# Sheet1.net
KiCad netlist of a schematic drawn in Altium Designer
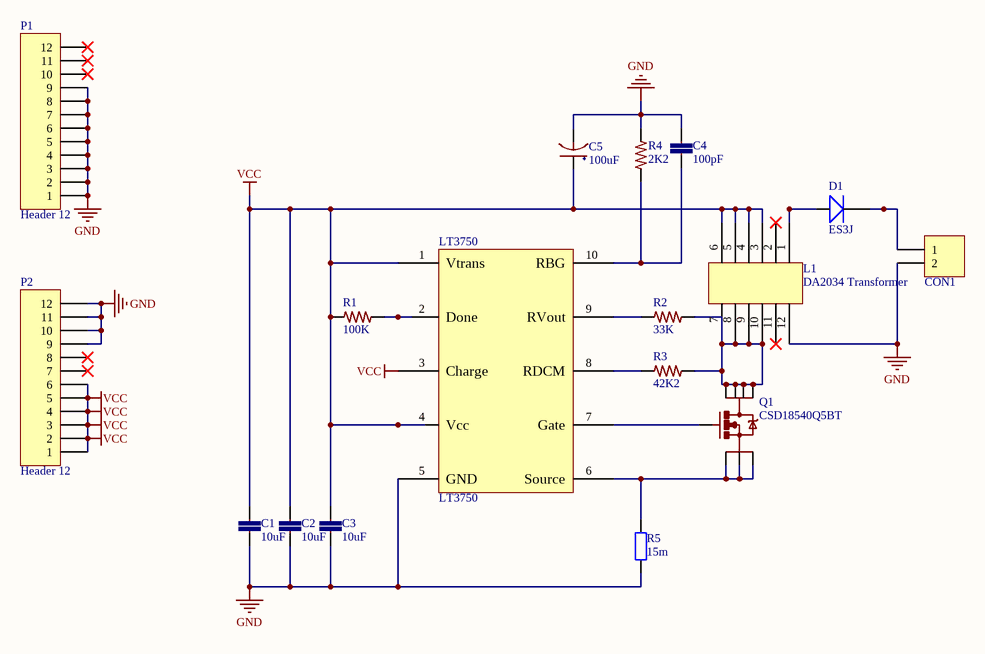
[diagram p0: Sheet1.SchDoc]

(export (version "E")
  (design (tool "Eeschema 10.0.6"))
  (components
    (comp (ref "C1")
      (value "10uF")
      (footprint "CAPC0603(1608)55_L")
      (description "CAP CER 10UF 16V X5R 0603")
      (fields (field (name "PART NO") "EMK107BBJ106MA-T"))
      (libsource (lib "IMBEL") (part "CAPACITOR"))
    )
    (comp (ref "C2")
      (value "10uF")
      (footprint "CAPC0603(1608)55_L")
      (description "CAP CER 10UF 16V X5R 0603")
      (fields (field (name "PART NO") "EMK107BBJ106MA-T"))
      (libsource (lib "IMBEL") (part "CAPACITOR"))
    )
    (comp (ref "C3")
      (value "10uF")
      (footprint "CAPC0603(1608)55_L")
      (description "CAP CER 10UF 16V X5R 0603")
      (fields (field (name "PART NO") "EMK107BBJ106MA-T"))
      (libsource (lib "IMBEL") (part "CAPACITOR"))
    )
    (comp (ref "C4")
      (value "100pF")
      (footprint "CAPC0603(1608)55_L")
      (description "CAP CER 100PF 50V NP0 0603")
      (fields (field (name "PART NO") "GRM1885C1H101JA01D"))
      (libsource (lib "IMBEL") (part "CAPACITOR"))
    )
    (comp (ref "C5")
      (value "100uF")
      (footprint "PCBComponent")
      (description "CAP ALUM 100UF 20% 80V SMD")
      (libsource (lib "IMBEL") (part "CAPACITOR-POL"))
    )
    (comp (ref "CON1")
      (value "OSTTA024163")
      (footprint "Term Block 2P")
      (description "2 Position Wire to Board Terminal Block Horizontal with Board 0.200\" (5.08mm) Through Hole")
      (libsource (lib "Schlib1") (part "Term Block 2P"))
    )
    (comp (ref "D1") (value "ES3J") (footprint "Diode") (libsource (lib "Schlib1") (part "Diode")))
    (comp (ref "L1")
      (value "DA2034 Transformer")
      (footprint "DA2034 Transformer")
      (libsource (lib "Schlib1") (part "DA2034 Transformer"))
    )
    (comp (ref "LT3750") (value "LT3750") (footprint "LT3750") (libsource (lib "Schlib1") (part "LT3750")))
    (comp (ref "P1")
      (value "Header 12")
      (footprint "HDR1X12")
      (description "Header, 12-Pin")
      (fields (field (name "PUBLISHER") "Altium Limited"))
      (libsource (lib "Miscellaneous Connectors") (part "Header 12"))
    )
    (comp (ref "P2")
      (value "Header 12")
      (footprint "HDR1X12")
      (description "Header, 12-Pin")
      (fields (field (name "PUBLISHER") "Altium Limited"))
      (libsource (lib "Miscellaneous Connectors") (part "Header 12"))
    )
    (comp (ref "Q1")
      (value "CSD18540Q5BT")
      (footprint "PCBComponent")
      (description "MOSFET N-CH 60V 100A 8VSON")
      (libsource (lib "IMBEL") (part "MOSFET-NCHANNEL"))
    )
    (comp (ref "R1")
      (value "100K")
      (footprint "0402-RES-HD")
      (description "RES 100K OHM 1/10W 1% 0402 SMD 1")
      (fields (field (name "PART NO") "ERJ-2GEJ104X"))
      (libsource (lib "IMBEL") (part "RESISTOR"))
    )
    (comp (ref "R2")
      (value "33K")
      (footprint "0402-RES-HD")
      (description "RES 33K OHM 1/10W 1% 0402 SMD")
      (fields (field (name "PART NO") "ERJ-2RKF3302X"))
      (libsource (lib "IMBEL") (part "RESISTOR"))
    )
    (comp (ref "R3")
      (value "42K2")
      (footprint "0402-RES-HD")
      (description "RES 42.2K OHM 1/10W 1% 0402 SMD")
      (fields (field (name "PART NO") "ERJ-2RKF4222X"))
      (libsource (lib "IMBEL") (part "RESISTOR"))
    )
    (comp (ref "R4")
      (value "2K2")
      (footprint "0402-RES-HD")
      (description "RES 2.2K OHM 1/10W 1% 0402 SMD")
      (fields (field (name "PART NO") "ERJ-2RKF2201X"))
      (libsource (lib "IMBEL") (part "RESISTOR"))
    )
    (comp (ref "R5")
      (value "15m")
      (footprint "RES-1206")
      (description "RES 15m OHM 1W 1% 1210 SMD")
      (fields (field (name "PUBLISHER") "Altium Limited"))
      (libsource (lib "Schlib1") (part "Res2"))
    )
  )
  (nets
    (net (code "1") (name "GND") (class "Default")
      (node (ref "C1") (pin "2") (pinfunction "2_2") (pintype "passive"))
      (node (ref "C2") (pin "2") (pinfunction "2_2") (pintype "passive"))
      (node (ref "C3") (pin "2") (pinfunction "2_2") (pintype "passive"))
      (node (ref "C4") (pin "1") (pinfunction "1_1") (pintype "passive"))
      (node (ref "C5") (pin "2") (pinfunction "-_2") (pintype "passive"))
      (node (ref "CON1") (pin "2") (pinfunction "2_2") (pintype "passive"))
      (node (ref "L1") (pin "12") (pinfunction "12_12") (pintype "passive"))
      (node (ref "LT3750") (pin "5") (pinfunction "GND_5") (pintype "passive"))
      (node (ref "P1") (pin "1") (pinfunction "1_1") (pintype "passive"))
      (node (ref "P1") (pin "2") (pinfunction "2_2") (pintype "passive"))
      (node (ref "P1") (pin "3") (pinfunction "3_3") (pintype "passive"))
      (node (ref "P1") (pin "4") (pinfunction "4_4") (pintype "passive"))
      (node (ref "P1") (pin "5") (pinfunction "5_5") (pintype "passive"))
      (node (ref "P1") (pin "6") (pinfunction "6_6") (pintype "passive"))
      (node (ref "P1") (pin "7") (pinfunction "7_7") (pintype "passive"))
      (node (ref "P1") (pin "8") (pinfunction "8_8") (pintype "passive"))
      (node (ref "P1") (pin "9") (pinfunction "9_9") (pintype "passive"))
      (node (ref "P2") (pin "10") (pinfunction "10_10") (pintype "passive"))
      (node (ref "P2") (pin "11") (pinfunction "11_11") (pintype "passive"))
      (node (ref "P2") (pin "12") (pinfunction "12_12") (pintype "passive"))
      (node (ref "P2") (pin "9") (pinfunction "9_9") (pintype "passive"))
      (node (ref "R4") (pin "2") (pinfunction "2_2") (pintype "passive"))
      (node (ref "R5") (pin "2") (pinfunction "2_2") (pintype "passive"))
    )
    (net (code "2") (name "Net-(CON1-Pad1)") (class "Default")
      (node (ref "CON1") (pin "1") (pinfunction "1_1") (pintype "passive"))
      (node (ref "D1") (pin "D1+") (pinfunction "D1+_D1+") (pintype "passive"))
    )
    (net (code "3") (name "Net-(D1-PadD1-)") (class "Default")
      (node (ref "D1") (pin "D1-") (pinfunction "D1-_D1-") (pintype "passive"))
      (node (ref "L1") (pin "1") (pinfunction "1_1") (pintype "passive"))
    )
    (net (code "4") (name "Net-(L1-Pad10)") (class "Default")
      (node (ref "L1") (pin "10") (pinfunction "10_10") (pintype "passive"))
      (node (ref "L1") (pin "7") (pinfunction "7_7") (pintype "passive"))
      (node (ref "L1") (pin "8") (pinfunction "8_8") (pintype "passive"))
      (node (ref "L1") (pin "9") (pinfunction "9_9") (pintype "passive"))
      (node (ref "Q1") (pin "5") (pinfunction "D_5") (pintype "passive"))
      (node (ref "Q1") (pin "6") (pinfunction "D_6") (pintype "passive"))
      (node (ref "Q1") (pin "7") (pinfunction "D_7") (pintype "passive"))
      (node (ref "Q1") (pin "8") (pinfunction "D_8") (pintype "passive"))
      (node (ref "R2") (pin "2") (pinfunction "2_2") (pintype "passive"))
      (node (ref "R3") (pin "1") (pinfunction "1_1") (pintype "passive"))
    )
    (net (code "5") (name "Net-(LT3750-Done)") (class "Default")
      (node (ref "LT3750") (pin "2") (pinfunction "Done_2") (pintype "passive"))
      (node (ref "R1") (pin "2") (pinfunction "2_2") (pintype "passive"))
    )
    (net (code "6") (name "Net-(LT3750-Gate)") (class "Default")
      (node (ref "LT3750") (pin "7") (pinfunction "Gate_7") (pintype "passive"))
      (node (ref "Q1") (pin "4") (pinfunction "G_4") (pintype "passive"))
    )
    (net (code "7") (name "Net-(LT3750-RBG)") (class "Default")
      (node (ref "C4") (pin "2") (pinfunction "2_2") (pintype "passive"))
      (node (ref "LT3750") (pin "10") (pinfunction "RBG_10") (pintype "passive"))
      (node (ref "R4") (pin "1") (pinfunction "1_1") (pintype "passive"))
    )
    (net (code "8") (name "Net-(LT3750-RDCM)") (class "Default")
      (node (ref "LT3750") (pin "8") (pinfunction "RDCM_8") (pintype "passive"))
      (node (ref "R3") (pin "2") (pinfunction "2_2") (pintype "passive"))
    )
    (net (code "9") (name "Net-(LT3750-RVout)") (class "Default")
      (node (ref "LT3750") (pin "9") (pinfunction "RVout_9") (pintype "passive"))
      (node (ref "R2") (pin "1") (pinfunction "1_1") (pintype "passive"))
    )
    (net (code "10") (name "Net-(LT3750-Source)") (class "Default")
      (node (ref "LT3750") (pin "6") (pinfunction "Source_6") (pintype "passive"))
      (node (ref "Q1") (pin "1") (pinfunction "S_1") (pintype "passive"))
      (node (ref "Q1") (pin "2") (pinfunction "S_2") (pintype "passive"))
      (node (ref "Q1") (pin "3") (pinfunction "S_3") (pintype "passive"))
      (node (ref "R5") (pin "1") (pinfunction "1_1") (pintype "passive"))
    )
    (net (code "11") (name "VCC") (class "Default")
      (node (ref "C1") (pin "1") (pinfunction "1_1") (pintype "passive"))
      (node (ref "C2") (pin "1") (pinfunction "1_1") (pintype "passive"))
      (node (ref "C3") (pin "1") (pinfunction "1_1") (pintype "passive"))
      (node (ref "C5") (pin "1") (pinfunction "+_1") (pintype "passive"))
      (node (ref "L1") (pin "3") (pinfunction "3_3") (pintype "passive"))
      (node (ref "L1") (pin "4") (pinfunction "4_4") (pintype "passive"))
      (node (ref "L1") (pin "5") (pinfunction "5_5") (pintype "passive"))
      (node (ref "L1") (pin "6") (pinfunction "6_6") (pintype "passive"))
      (node (ref "LT3750") (pin "1") (pinfunction "Vtrans_1") (pintype "passive"))
      (node (ref "LT3750") (pin "3") (pinfunction "Charge_3") (pintype "passive"))
      (node (ref "LT3750") (pin "4") (pinfunction "Vcc_4") (pintype "passive"))
      (node (ref "P2") (pin "1") (pinfunction "1_1") (pintype "passive"))
      (node (ref "P2") (pin "2") (pinfunction "2_2") (pintype "passive"))
      (node (ref "P2") (pin "3") (pinfunction "3_3") (pintype "passive"))
      (node (ref "P2") (pin "4") (pinfunction "4_4") (pintype "passive"))
      (node (ref "P2") (pin "5") (pinfunction "5_5") (pintype "passive"))
      (node (ref "P2") (pin "6") (pinfunction "6_6") (pintype "passive"))
      (node (ref "R1") (pin "1") (pinfunction "1_1") (pintype "passive"))
    )
    (net (code "12") (name "unconnected-(L1-Pad2)") (class "Default")
      (node (ref "L1") (pin "2") (pinfunction "2_2") (pintype "passive+no_connect"))
    )
    (net (code "13") (name "unconnected-(L1-Pad11)") (class "Default")
      (node (ref "L1") (pin "11") (pinfunction "11_11") (pintype "passive+no_connect"))
    )
    (net (code "14") (name "unconnected-(P1-Pad10)") (class "Default")
      (node (ref "P1") (pin "10") (pinfunction "10_10") (pintype "passive+no_connect"))
    )
    (net (code "15") (name "unconnected-(P1-Pad11)") (class "Default")
      (node (ref "P1") (pin "11") (pinfunction "11_11") (pintype "passive+no_connect"))
    )
    (net (code "16") (name "unconnected-(P1-Pad12)") (class "Default")
      (node (ref "P1") (pin "12") (pinfunction "12_12") (pintype "passive+no_connect"))
    )
    (net (code "17") (name "unconnected-(P2-Pad7)") (class "Default")
      (node (ref "P2") (pin "7") (pinfunction "7_7") (pintype "passive+no_connect"))
    )
    (net (code "18") (name "unconnected-(P2-Pad8)") (class "Default")
      (node (ref "P2") (pin "8") (pinfunction "8_8") (pintype "passive+no_connect"))
    )
  )
)
